# Monitoring_IC.net
KiCad netlist of a schematic drawn in Altium Designer
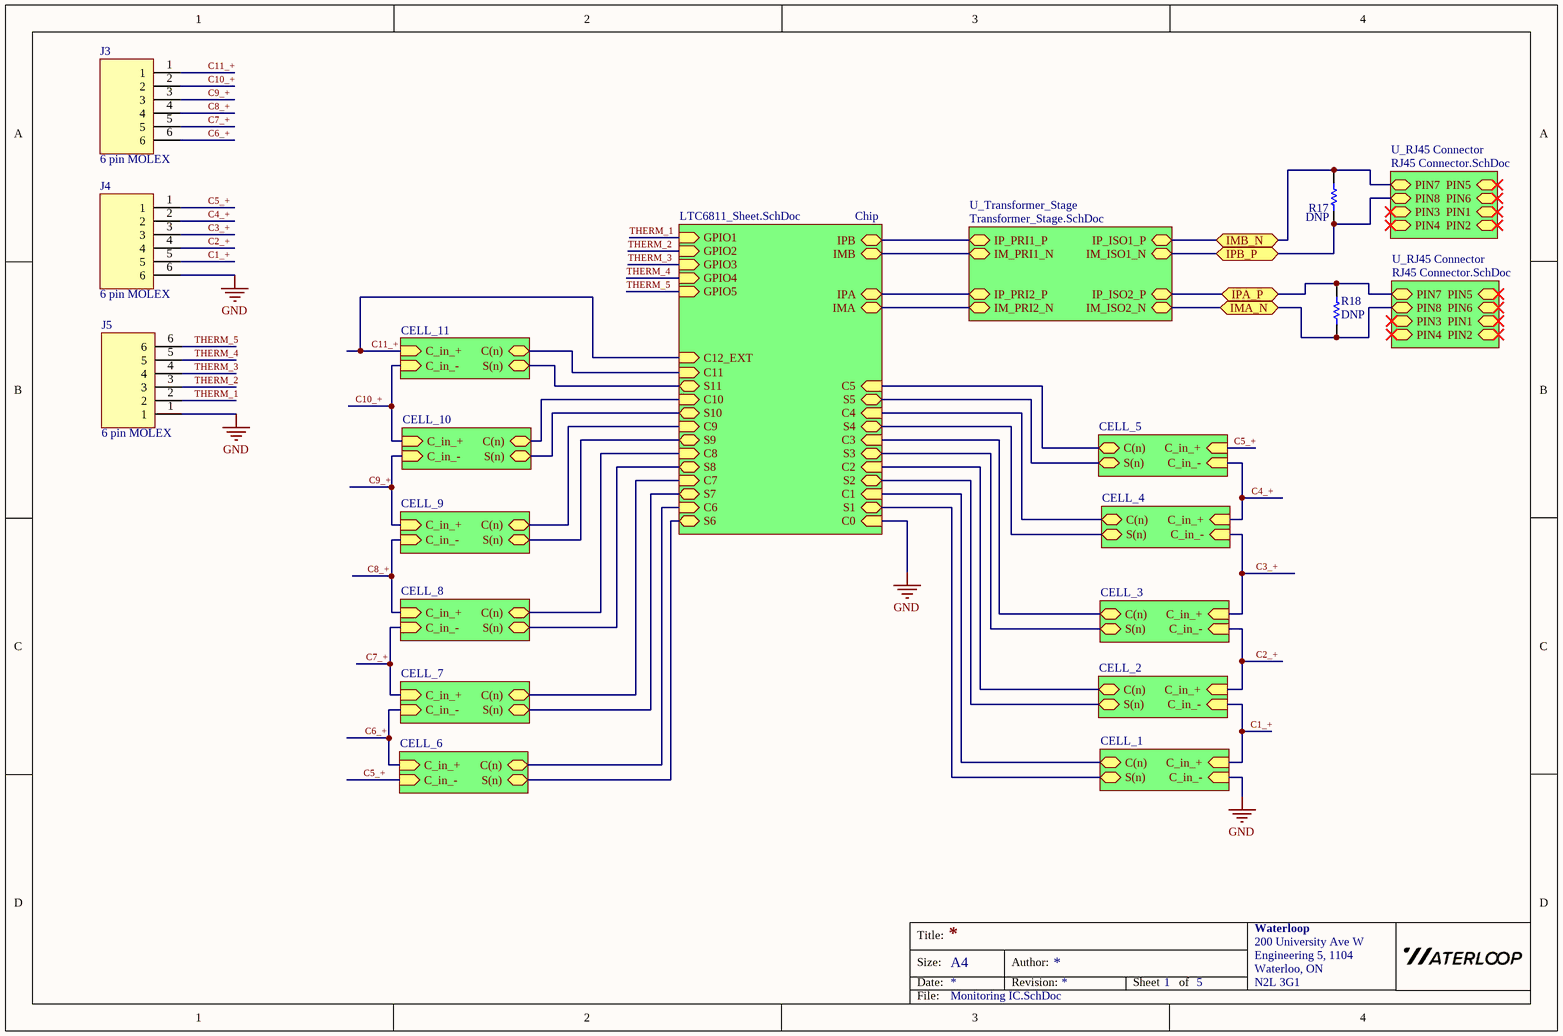
[diagram p0: Monitoring IC.SchDoc]

(export (version "E")
  (design (tool "Eeschema 10.0.6"))
  (components
    (comp (ref "J3")
      (value "6 pin MOLEX")
      (footprint "1726480106")
      (description "1x6 MOLEX MiniFit Jr. Connector")
      (libsource (lib "GeneralConnectors") (part "MOLEX1726480106"))
    )
    (comp (ref "J4")
      (value "6 pin MOLEX")
      (footprint "1726480106")
      (description "1x6 MOLEX MiniFit Jr. Connector")
      (libsource (lib "GeneralConnectors") (part "MOLEX1726480106"))
    )
    (comp (ref "J5")
      (value "6 pin MOLEX")
      (footprint "1726480106")
      (description "1x6 MOLEX MiniFit Jr. Connector")
      (libsource (lib "") (part "MOLEX1726480106_1"))
    )
    (comp (ref "R17")
      (value "DNP")
      (footprint "0805 - Resistor")
      (description "Resistor")
      (libsource (lib "General") (part "Resistor"))
    )
    (comp (ref "R18")
      (value "DNP")
      (footprint "0805 - Resistor")
      (description "Resistor")
      (libsource (lib "General") (part "Resistor"))
    )
  )
  (nets
    (net (code "12") (name "/C1_+") (class "Default")
      (node (ref "J4") (pin "5") (pinfunction "5_5") (pintype "passive"))
    )
    (net (code "13") (name "/C2_+") (class "Default")
      (node (ref "J4") (pin "4") (pinfunction "4_4") (pintype "passive"))
    )
    (net (code "14") (name "/C3_+") (class "Default")
      (node (ref "J4") (pin "3") (pinfunction "3_3") (pintype "passive"))
    )
    (net (code "15") (name "/C4_+") (class "Default")
      (node (ref "J4") (pin "2") (pinfunction "2_2") (pintype "passive"))
    )
    (net (code "16") (name "/C5_+") (class "Default")
      (node (ref "J4") (pin "1") (pinfunction "1_1") (pintype "passive"))
    )
    (net (code "17") (name "/C6_+") (class "Default")
      (node (ref "J3") (pin "6") (pinfunction "6_6") (pintype "passive"))
    )
    (net (code "18") (name "/C7_+") (class "Default")
      (node (ref "J3") (pin "5") (pinfunction "5_5") (pintype "passive"))
    )
    (net (code "19") (name "/C8_+") (class "Default")
      (node (ref "J3") (pin "4") (pinfunction "4_4") (pintype "passive"))
    )
    (net (code "20") (name "/C9_+") (class "Default")
      (node (ref "J3") (pin "3") (pinfunction "3_3") (pintype "passive"))
    )
    (net (code "21") (name "/C10_+") (class "Default")
      (node (ref "J3") (pin "2") (pinfunction "2_2") (pintype "passive"))
    )
    (net (code "22") (name "/C11_+") (class "Default")
      (node (ref "J3") (pin "1") (pinfunction "1_1") (pintype "passive"))
    )
    (net (code "24") (name "/IMA_N") (class "Default")
      (node (ref "R18") (pin "2") (pinfunction "2_2") (pintype "passive"))
    )
    (net (code "26") (name "/IMB_N") (class "Default")
      (node (ref "R17") (pin "2") (pinfunction "2_2") (pintype "passive"))
    )
    (net (code "28") (name "/IPA_P") (class "Default")
      (node (ref "R18") (pin "1") (pinfunction "1_1") (pintype "passive"))
    )
    (net (code "30") (name "/IPB_P") (class "Default")
      (node (ref "R17") (pin "1") (pinfunction "1_1") (pintype "passive"))
    )
    (net (code "54") (name "/THERM_1") (class "Default")
      (node (ref "J5") (pin "2") (pinfunction "2_2") (pintype "passive"))
    )
    (net (code "55") (name "/THERM_2") (class "Default")
      (node (ref "J5") (pin "3") (pinfunction "3_3") (pintype "passive"))
    )
    (net (code "56") (name "/THERM_3") (class "Default")
      (node (ref "J5") (pin "4") (pinfunction "4_4") (pintype "passive"))
    )
    (net (code "57") (name "/THERM_4") (class "Default")
      (node (ref "J5") (pin "5") (pinfunction "5_5") (pintype "passive"))
    )
    (net (code "58") (name "/THERM_5") (class "Default")
      (node (ref "J5") (pin "6") (pinfunction "6_6") (pintype "passive"))
    )
    (net (code "59") (name "GND") (class "Default")
      (node (ref "J4") (pin "6") (pinfunction "6_6") (pintype "passive"))
      (node (ref "J5") (pin "1") (pinfunction "1_1") (pintype "passive"))
    )
  )
)
